# schematic.net
KiCad netlist of a schematic drawn in Altium Designer
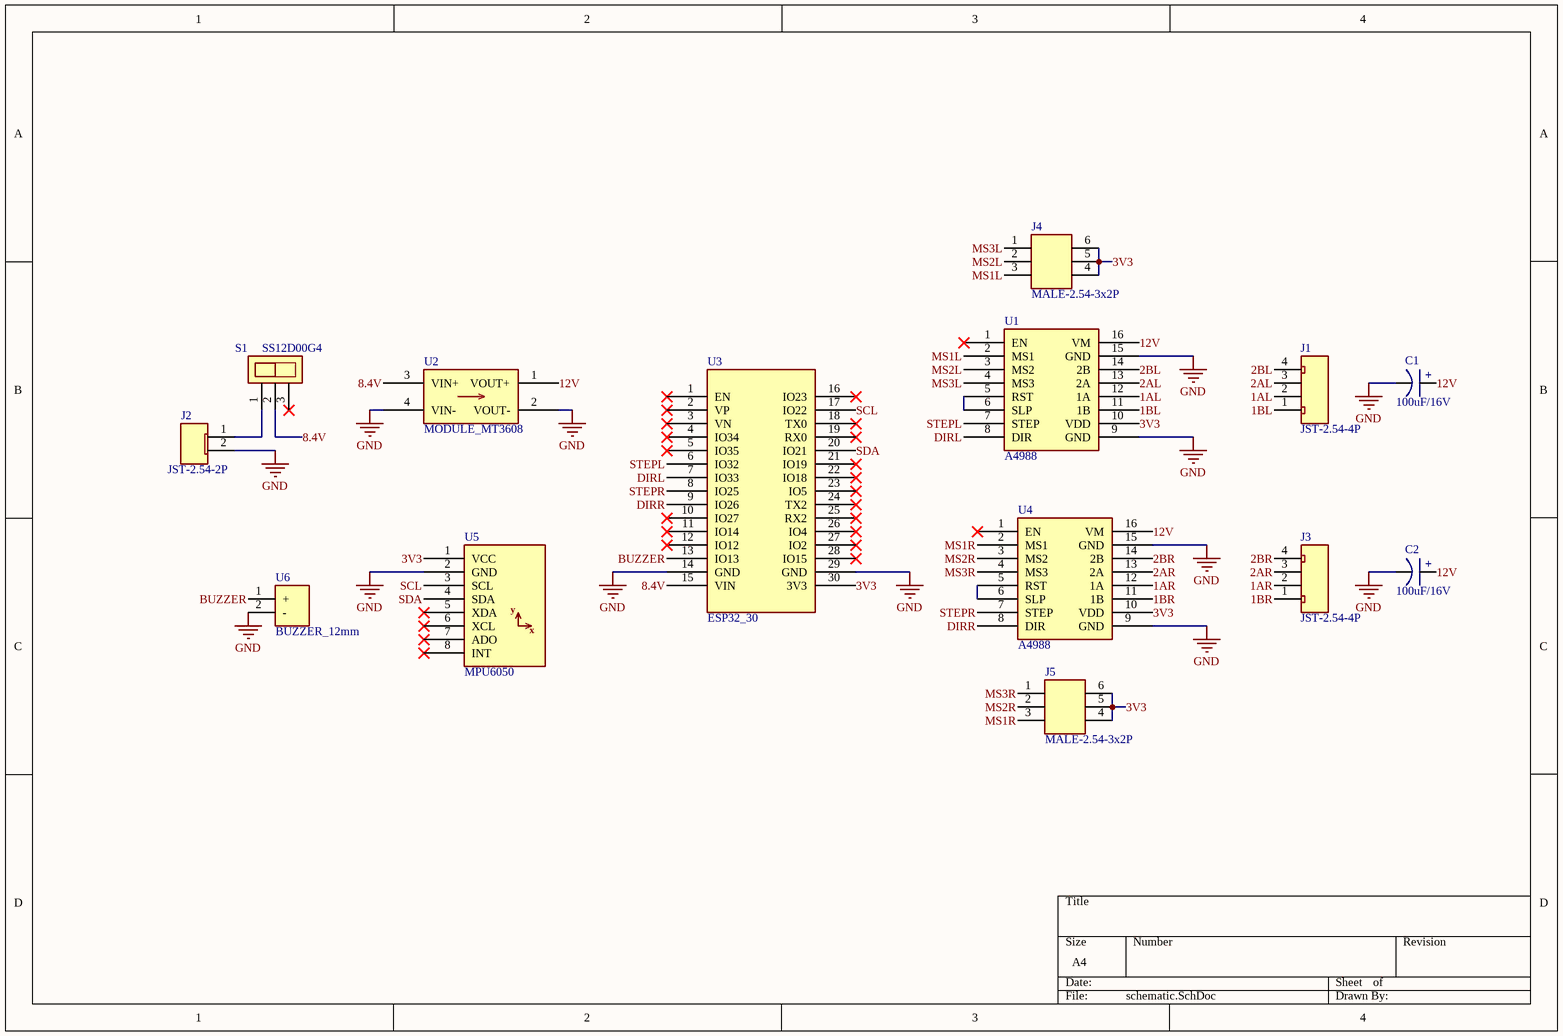
[diagram p0: schematic.SchDoc]

(export (version "E")
  (design (tool "Eeschema 10.0.6"))
  (components
    (comp (ref "C1")
      (value "100uF/16V")
      (footprint "100uF/16V")
      (description "Electrolytic Capacitor 100uF/16V")
      (libsource (lib "Electrolytic Capacitor") (part "100uF/16V"))
    )
    (comp (ref "C2")
      (value "100uF/16V")
      (footprint "100uF/16V")
      (description "Electrolytic Capacitor 100uF/16V")
      (libsource (lib "Electrolytic Capacitor") (part "100uF/16V"))
    )
    (comp (ref "J1")
      (value "JST-2.54-4P")
      (footprint "JST-2.54-4P")
      (description "Female Connector JST 4 Vias, 2.54mm.")
      (libsource (lib "Connectors") (part "JST-2.54-4P"))
    )
    (comp (ref "J2")
      (value "JST-2.54-2P")
      (footprint "JST-2.54-2P")
      (description "Female Connector JST 2 Vias, 2.54mm.")
      (libsource (lib "Connectors") (part "JST-2.54-2P"))
    )
    (comp (ref "J3")
      (value "JST-2.54-4P")
      (footprint "JST-2.54-4P")
      (description "Female Connector JST 4 Vias, 2.54mm.")
      (libsource (lib "Connectors") (part "JST-2.54-4P"))
    )
    (comp (ref "J4")
      (value "MALE-2.54-3x2P")
      (footprint "MALE-2.54-3x2P")
      (description "Male Header Connector 2.54mm 3x2 Pins.")
      (libsource (lib "Connectors") (part "MALE-2.54-3x2P"))
    )
    (comp (ref "J5")
      (value "MALE-2.54-3x2P")
      (footprint "MALE-2.54-3x2P")
      (description "Male Header Connector 2.54mm 3x2 Pins.")
      (libsource (lib "Connectors") (part "MALE-2.54-3x2P"))
    )
    (comp (ref "S1")
      (value "SS12D00G4")
      (footprint "SS12D00G4")
      (libsource (lib "Buttons & Switches") (part "SS12D00G4"))
    )
    (comp (ref "U1")
      (value "A4988")
      (footprint "A4988")
      (description "Module Stepper Motor Driver 8-35V 2A 20x15mm")
      (libsource (lib "Motor Drivers") (part "A4988"))
    )
    (comp (ref "U2")
      (value "MODULE_MT3608")
      (footprint "MODULE_MT3608")
      (description "MODULE BUCK STEP UP 2A 37x17mm")
      (libsource (lib "Voltage Regulators") (part "MODULE_MT3608"))
    )
    (comp (ref "U3")
      (value "ESP32_30")
      (footprint "ESP32_30")
      (description "Microcontoller Board 30 Pins Wifi 2.4GHz BLE 4.2 ESP32-WROOM-32D")
      (libsource (lib "Espressif Microcontrollers") (part "ESP32_30"))
    )
    (comp (ref "U4")
      (value "A4988")
      (footprint "A4988")
      (description "Module Stepper Motor Driver 8-35V 2A 20x15mm")
      (libsource (lib "Motor Drivers") (part "A4988"))
    )
    (comp (ref "U5")
      (value "MPU6050")
      (footprint "MPU6050")
      (description "IMU ACCEL/GYRO 3-AXIS I2C")
      (libsource (lib "Sensors") (part "MPU6050"))
    )
    (comp (ref "U6")
      (value "BUZZER_12mm")
      (footprint "BUZZER_12mm")
      (description "BUZZER MAGNETIC 12MM")
      (libsource (lib "Random") (part "BUZZER_12mm"))
    )
  )
  (nets
    (net (code "1") (name "/1AL") (class "Default")
      (node (ref "J1") (pin "2") (pintype "passive"))
      (node (ref "U1") (pin "12") (pinfunction "1A_12") (pintype "passive"))
    )
    (net (code "2") (name "/1AR") (class "Default")
      (node (ref "J3") (pin "2") (pintype "passive"))
      (node (ref "U4") (pin "12") (pinfunction "1A_12") (pintype "passive"))
    )
    (net (code "3") (name "/1BL") (class "Default")
      (node (ref "J1") (pin "1") (pintype "passive"))
      (node (ref "U1") (pin "11") (pinfunction "1B_11") (pintype "passive"))
    )
    (net (code "4") (name "/1BR") (class "Default")
      (node (ref "J3") (pin "1") (pintype "passive"))
      (node (ref "U4") (pin "11") (pinfunction "1B_11") (pintype "passive"))
    )
    (net (code "5") (name "/2AL") (class "Default")
      (node (ref "J1") (pin "3") (pintype "passive"))
      (node (ref "U1") (pin "13") (pinfunction "2A_13") (pintype "passive"))
    )
    (net (code "6") (name "/2AR") (class "Default")
      (node (ref "J3") (pin "3") (pintype "passive"))
      (node (ref "U4") (pin "13") (pinfunction "2A_13") (pintype "passive"))
    )
    (net (code "7") (name "/2BL") (class "Default")
      (node (ref "J1") (pin "4") (pintype "passive"))
      (node (ref "U1") (pin "14") (pinfunction "2B_14") (pintype "passive"))
    )
    (net (code "8") (name "/2BR") (class "Default")
      (node (ref "J3") (pin "4") (pintype "passive"))
      (node (ref "U4") (pin "14") (pinfunction "2B_14") (pintype "passive"))
    )
    (net (code "9") (name "/3V3") (class "Default")
      (node (ref "J4") (pin "4") (pintype "passive"))
      (node (ref "J4") (pin "5") (pintype "passive"))
      (node (ref "J4") (pin "6") (pintype "passive"))
      (node (ref "J5") (pin "4") (pintype "passive"))
      (node (ref "J5") (pin "5") (pintype "passive"))
      (node (ref "J5") (pin "6") (pintype "passive"))
      (node (ref "U1") (pin "10") (pinfunction "VDD_10") (pintype "passive"))
      (node (ref "U3") (pin "30") (pinfunction "3V3_30") (pintype "passive"))
      (node (ref "U4") (pin "10") (pinfunction "VDD_10") (pintype "passive"))
      (node (ref "U5") (pin "1") (pinfunction "VCC_1") (pintype "passive"))
    )
    (net (code "10") (name "/8.4V") (class "Default")
      (node (ref "S1") (pin "2") (pintype "passive"))
      (node (ref "U2") (pin "3") (pinfunction "VIN+_3") (pintype "passive"))
      (node (ref "U3") (pin "15") (pinfunction "VIN_15") (pintype "passive"))
    )
    (net (code "11") (name "/12V") (class "Default")
      (node (ref "C1") (pin "2") (pinfunction "_2_2") (pintype "passive"))
      (node (ref "C2") (pin "2") (pinfunction "_2_2") (pintype "passive"))
      (node (ref "U1") (pin "16") (pinfunction "VM_16") (pintype "passive"))
      (node (ref "U2") (pin "1") (pinfunction "VOUT+_1") (pintype "passive"))
      (node (ref "U4") (pin "16") (pinfunction "VM_16") (pintype "passive"))
    )
    (net (code "12") (name "/BUZZER") (class "Default")
      (node (ref "U3") (pin "13") (pinfunction "IO13_13") (pintype "passive"))
      (node (ref "U6") (pin "1") (pinfunction "+_1") (pintype "passive"))
    )
    (net (code "13") (name "/DIRL") (class "Default")
      (node (ref "U1") (pin "8") (pinfunction "DIR_8") (pintype "passive"))
      (node (ref "U3") (pin "7") (pinfunction "IO33_7") (pintype "passive"))
    )
    (net (code "14") (name "/DIRR") (class "Default")
      (node (ref "U3") (pin "9") (pinfunction "IO26_9") (pintype "passive"))
      (node (ref "U4") (pin "8") (pinfunction "DIR_8") (pintype "passive"))
    )
    (net (code "15") (name "/MS1L") (class "Default")
      (node (ref "J4") (pin "3") (pintype "passive"))
      (node (ref "U1") (pin "2") (pinfunction "MS1_2") (pintype "passive"))
    )
    (net (code "16") (name "/MS1R") (class "Default")
      (node (ref "J5") (pin "3") (pintype "passive"))
      (node (ref "U4") (pin "2") (pinfunction "MS1_2") (pintype "passive"))
    )
    (net (code "17") (name "/MS2L") (class "Default")
      (node (ref "J4") (pin "2") (pintype "passive"))
      (node (ref "U1") (pin "3") (pinfunction "MS2_3") (pintype "passive"))
    )
    (net (code "18") (name "/MS2R") (class "Default")
      (node (ref "J5") (pin "2") (pintype "passive"))
      (node (ref "U4") (pin "3") (pinfunction "MS2_3") (pintype "passive"))
    )
    (net (code "19") (name "/MS3L") (class "Default")
      (node (ref "J4") (pin "1") (pintype "passive"))
      (node (ref "U1") (pin "4") (pinfunction "MS3_4") (pintype "passive"))
    )
    (net (code "20") (name "/MS3R") (class "Default")
      (node (ref "J5") (pin "1") (pintype "passive"))
      (node (ref "U4") (pin "4") (pinfunction "MS3_4") (pintype "passive"))
    )
    (net (code "21") (name "/SCL") (class "Default")
      (node (ref "U3") (pin "17") (pinfunction "IO22_17") (pintype "passive"))
      (node (ref "U5") (pin "3") (pinfunction "SCL_3") (pintype "passive"))
    )
    (net (code "22") (name "/SDA") (class "Default")
      (node (ref "U3") (pin "20") (pinfunction "IO21_20") (pintype "passive"))
      (node (ref "U5") (pin "4") (pinfunction "SDA_4") (pintype "passive"))
    )
    (net (code "23") (name "/STEPL") (class "Default")
      (node (ref "U1") (pin "7") (pinfunction "STEP_7") (pintype "passive"))
      (node (ref "U3") (pin "6") (pinfunction "IO32_6") (pintype "passive"))
    )
    (net (code "24") (name "/STEPR") (class "Default")
      (node (ref "U3") (pin "8") (pinfunction "IO25_8") (pintype "passive"))
      (node (ref "U4") (pin "7") (pinfunction "STEP_7") (pintype "passive"))
    )
    (net (code "25") (name "GND") (class "Default")
      (node (ref "C1") (pin "1") (pinfunction "1_1") (pintype "passive"))
      (node (ref "C2") (pin "1") (pinfunction "1_1") (pintype "passive"))
      (node (ref "J2") (pin "2") (pintype "passive"))
      (node (ref "U1") (pin "15") (pinfunction "GND_15") (pintype "passive"))
      (node (ref "U1") (pin "9") (pinfunction "GND_9") (pintype "passive"))
      (node (ref "U2") (pin "2") (pinfunction "VOUT-_2") (pintype "passive"))
      (node (ref "U2") (pin "4") (pinfunction "VIN-_4") (pintype "passive"))
      (node (ref "U3") (pin "14") (pinfunction "GND_14") (pintype "passive"))
      (node (ref "U3") (pin "29") (pinfunction "GND_29") (pintype "passive"))
      (node (ref "U4") (pin "15") (pinfunction "GND_15") (pintype "passive"))
      (node (ref "U4") (pin "9") (pinfunction "GND_9") (pintype "passive"))
      (node (ref "U5") (pin "2") (pinfunction "GND_2") (pintype "passive"))
      (node (ref "U6") (pin "2") (pinfunction "-_2") (pintype "passive"))
    )
    (net (code "26") (name "Net-(J2-Pad1)") (class "Default")
      (node (ref "J2") (pin "1") (pintype "passive"))
      (node (ref "S1") (pin "1") (pintype "passive"))
    )
    (net (code "27") (name "Net-(U1-RST)") (class "Default")
      (node (ref "U1") (pin "5") (pinfunction "RST_5") (pintype "passive"))
      (node (ref "U1") (pin "6") (pinfunction "SLP_6") (pintype "passive"))
    )
    (net (code "28") (name "Net-(U4-RST)") (class "Default")
      (node (ref "U4") (pin "5") (pinfunction "RST_5") (pintype "passive"))
      (node (ref "U4") (pin "6") (pinfunction "SLP_6") (pintype "passive"))
    )
    (net (code "29") (name "unconnected-(S1-Pad3)") (class "Default")
      (node (ref "S1") (pin "3") (pintype "passive+no_connect"))
    )
    (net (code "30") (name "unconnected-(U1-EN-Pad1)") (class "Default")
      (node (ref "U1") (pin "1") (pinfunction "EN_1") (pintype "passive+no_connect"))
    )
    (net (code "31") (name "unconnected-(U3-EN-Pad1)") (class "Default")
      (node (ref "U3") (pin "1") (pinfunction "EN_1") (pintype "passive+no_connect"))
    )
    (net (code "32") (name "unconnected-(U3-IO2-Pad27)") (class "Default")
      (node (ref "U3") (pin "27") (pinfunction "IO2_27") (pintype "passive+no_connect"))
    )
    (net (code "33") (name "unconnected-(U3-IO4-Pad26)") (class "Default")
      (node (ref "U3") (pin "26") (pinfunction "IO4_26") (pintype "passive+no_connect"))
    )
    (net (code "34") (name "unconnected-(U3-IO5-Pad23)") (class "Default")
      (node (ref "U3") (pin "23") (pinfunction "IO5_23") (pintype "passive+no_connect"))
    )
    (net (code "35") (name "unconnected-(U3-IO12-Pad12)") (class "Default")
      (node (ref "U3") (pin "12") (pinfunction "IO12_12") (pintype "passive+no_connect"))
    )
    (net (code "36") (name "unconnected-(U3-IO14-Pad11)") (class "Default")
      (node (ref "U3") (pin "11") (pinfunction "IO14_11") (pintype "passive+no_connect"))
    )
    (net (code "37") (name "unconnected-(U3-IO15-Pad28)") (class "Default")
      (node (ref "U3") (pin "28") (pinfunction "IO15_28") (pintype "passive+no_connect"))
    )
    (net (code "38") (name "unconnected-(U3-IO18-Pad22)") (class "Default")
      (node (ref "U3") (pin "22") (pinfunction "IO18_22") (pintype "passive+no_connect"))
    )
    (net (code "39") (name "unconnected-(U3-IO19-Pad21)") (class "Default")
      (node (ref "U3") (pin "21") (pinfunction "IO19_21") (pintype "passive+no_connect"))
    )
    (net (code "40") (name "unconnected-(U3-IO23-Pad16)") (class "Default")
      (node (ref "U3") (pin "16") (pinfunction "IO23_16") (pintype "passive+no_connect"))
    )
    (net (code "41") (name "unconnected-(U3-IO27-Pad10)") (class "Default")
      (node (ref "U3") (pin "10") (pinfunction "IO27_10") (pintype "passive+no_connect"))
    )
    (net (code "42") (name "unconnected-(U3-IO34-Pad4)") (class "Default")
      (node (ref "U3") (pin "4") (pinfunction "IO34_4") (pintype "passive+no_connect"))
    )
    (net (code "43") (name "unconnected-(U3-IO35-Pad5)") (class "Default")
      (node (ref "U3") (pin "5") (pinfunction "IO35_5") (pintype "passive+no_connect"))
    )
    (net (code "44") (name "unconnected-(U3-RX0-Pad19)") (class "Default")
      (node (ref "U3") (pin "19") (pinfunction "RX0_19") (pintype "passive+no_connect"))
    )
    (net (code "45") (name "unconnected-(U3-RX2-Pad25)") (class "Default")
      (node (ref "U3") (pin "25") (pinfunction "RX2_25") (pintype "passive+no_connect"))
    )
    (net (code "46") (name "unconnected-(U3-TX0-Pad18)") (class "Default")
      (node (ref "U3") (pin "18") (pinfunction "TX0_18") (pintype "passive+no_connect"))
    )
    (net (code "47") (name "unconnected-(U3-TX2-Pad24)") (class "Default")
      (node (ref "U3") (pin "24") (pinfunction "TX2_24") (pintype "passive+no_connect"))
    )
    (net (code "48") (name "unconnected-(U3-VN-Pad3)") (class "Default")
      (node (ref "U3") (pin "3") (pinfunction "VN_3") (pintype "passive+no_connect"))
    )
    (net (code "49") (name "unconnected-(U3-VP-Pad2)") (class "Default")
      (node (ref "U3") (pin "2") (pinfunction "VP_2") (pintype "passive+no_connect"))
    )
    (net (code "50") (name "unconnected-(U4-EN-Pad1)") (class "Default")
      (node (ref "U4") (pin "1") (pinfunction "EN_1") (pintype "passive+no_connect"))
    )
    (net (code "51") (name "unconnected-(U5-ADO-Pad7)") (class "Default")
      (node (ref "U5") (pin "7") (pinfunction "ADO_7") (pintype "passive+no_connect"))
    )
    (net (code "52") (name "unconnected-(U5-INT-Pad8)") (class "Default")
      (node (ref "U5") (pin "8") (pinfunction "INT_8") (pintype "passive+no_connect"))
    )
    (net (code "53") (name "unconnected-(U5-XCL-Pad6)") (class "Default")
      (node (ref "U5") (pin "6") (pinfunction "XCL_6") (pintype "passive+no_connect"))
    )
    (net (code "54") (name "unconnected-(U5-XDA-Pad5)") (class "Default")
      (node (ref "U5") (pin "5") (pinfunction "XDA_5") (pintype "passive+no_connect"))
    )
  )
)
